# transmitter.net
KiCad netlist of a schematic drawn in Altium Designer
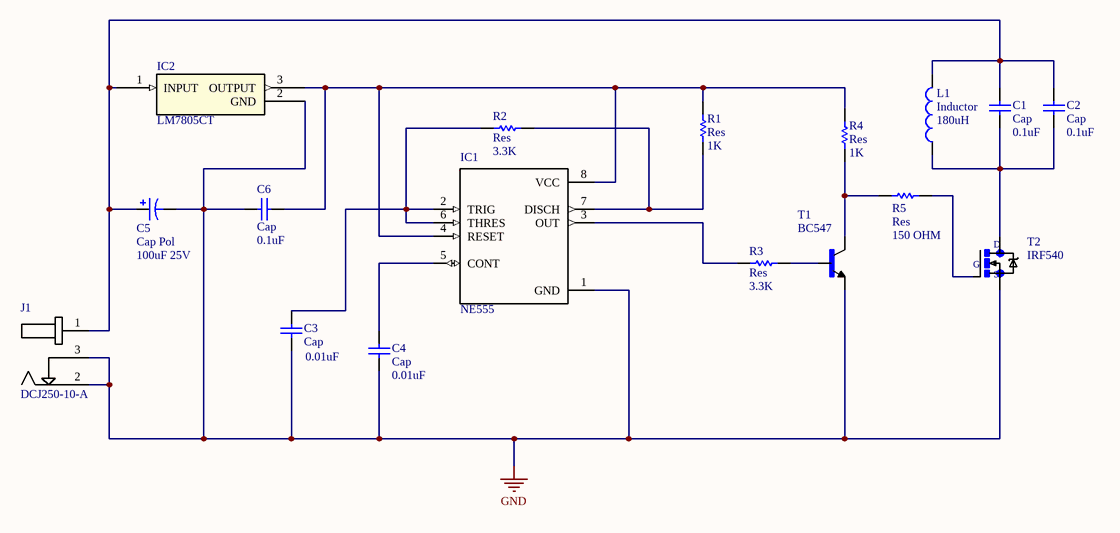
[diagram p0: transmitter.SchDoc]

(export (version "E")
  (design (tool "Eeschema 10.0.6"))
  (components
    (comp (ref "C1")
      (value "Cap")
      (footprint "RAD-0.3")
      (description "Capacitor")
      (fields (field (name "ALTIUM_VALUE") "0.1uF") (field (name "PUBLISHER") "Altium Limited"))
      (libsource (lib "Miscellaneous Devices") (part "Cap"))
    )
    (comp (ref "C2")
      (value "Cap")
      (footprint "RAD-0.3")
      (description "Capacitor")
      (fields (field (name "ALTIUM_VALUE") "0.1uF") (field (name "PUBLISHER") "Altium Limited"))
      (libsource (lib "Miscellaneous Devices") (part "Cap"))
    )
    (comp (ref "C3")
      (value "Cap")
      (footprint "RAD-0.3")
      (description "Capacitor")
      (fields (field (name "ALTIUM_VALUE") "0.01uF") (field (name "PUBLISHER") "Altium Limited"))
      (libsource (lib "Miscellaneous Devices") (part "Cap"))
    )
    (comp (ref "C4")
      (value "Cap")
      (footprint "RAD-0.3")
      (description "Capacitor")
      (fields (field (name "ALTIUM_VALUE") "0.01uF") (field (name "PUBLISHER") "Altium Limited"))
      (libsource (lib "Miscellaneous Devices") (part "Cap"))
    )
    (comp (ref "C5")
      (value "Cap Pol")
      (footprint "RB7.6-15")
      (description "Polarized Capacitor (Radial)")
      (fields (field (name "ALTIUM_VALUE") "100uF 25V") (field (name "PUBLISHER") "Altium Limited"))
      (libsource (lib "Miscellaneous Devices") (part "Cap Pol1"))
    )
    (comp (ref "C6")
      (value "Cap")
      (footprint "RAD-0.3")
      (description "Capacitor")
      (fields (field (name "ALTIUM_VALUE") "0.1uF") (field (name "PUBLISHER") "Altium Limited"))
      (libsource (lib "Miscellaneous Devices") (part "Cap"))
    )
    (comp (ref "IC1")
      (value "NE555")
      (footprint "NE555P:DIP8")
      (description "Precision timing circuits capable of producing accurate time delays or oscillation")
      (fields (field (name "MF") "Texas Instruments"))
      (libsource (lib "NE555") (part "NE555"))
    )
    (comp (ref "IC2")
      (value "LM7805CT")
      (footprint "LM7805CT:TO-220")
      (description "Imported")
      (libsource (lib "LM7805CT") (part "LM7805CT"))
    )
    (comp (ref "J1")
      (value "DCJ250-10-A")
      (footprint "DCJ250-10-A-XX-X_revA:DCJ250-10-A_XX-X_revA")
      (description "DC Power Jack, Thru-Hole, Horizontal, with Locating Pegs, D2.5mm")
      (libsource (lib "DCJ250-10-A_XX-X_revA") (part "DCJ250-10-A_XX-X_revA"))
    )
    (comp (ref "L1")
      (value "Inductor")
      (footprint "HDR1X2")
      (fields (field (name "ALTIUM_VALUE") "180uH") (field (name "PUBLISHER") "Altium Limited"))
      (libsource (lib "Miscellaneous Devices") (part "Inductor"))
    )
    (comp (ref "R1")
      (value "Res")
      (footprint "AXIAL-0.3")
      (description "Resistor")
      (fields (field (name "ALTIUM_VALUE") "1K") (field (name "PUBLISHER") "Altium Limited"))
      (libsource (lib "Miscellaneous Devices") (part "Res1"))
    )
    (comp (ref "R2")
      (value "Res")
      (footprint "AXIAL-0.3")
      (description "Resistor")
      (fields (field (name "ALTIUM_VALUE") "3.3K") (field (name "PUBLISHER") "Altium Limited"))
      (libsource (lib "Miscellaneous Devices") (part "Res1"))
    )
    (comp (ref "R3")
      (value "Res")
      (footprint "AXIAL-0.3")
      (description "Resistor")
      (fields (field (name "ALTIUM_VALUE") "3.3K") (field (name "PUBLISHER") "Altium Limited"))
      (libsource (lib "Miscellaneous Devices") (part "Res1"))
    )
    (comp (ref "R4")
      (value "Res")
      (footprint "AXIAL-0.3")
      (description "Resistor")
      (fields (field (name "ALTIUM_VALUE") "1K") (field (name "PUBLISHER") "Altium Limited"))
      (libsource (lib "Miscellaneous Devices") (part "Res1"))
    )
    (comp (ref "R5")
      (value "Res")
      (footprint "AXIAL-0.3")
      (description "Resistor")
      (fields (field (name "ALTIUM_VALUE") "150 OHM") (field (name "PUBLISHER") "Altium Limited"))
      (libsource (lib "Miscellaneous Devices") (part "Res1"))
    )
    (comp (ref "T1")
      (value "BC547")
      (footprint "TO-92")
      (description "Transistor NPN BC547 PHILIPS miliampere=100 TO92")
      (fields (field (name "MF") "ON Semiconductor"))
      (libsource (lib "BC547") (part "BC547"))
    )
    (comp (ref "T2")
      (value "IRF540")
      (footprint "TO220BV_IRF540(Primary)")
      (fields (field (name "MF") "Vishay Siliconix"))
      (libsource (lib "IRF540") (part "IRF540"))
    )
  )
  (nets
    (net (code "1") (name "GND") (class "Default")
      (node (ref "C3") (pin "1") (pinfunction "1_1") (pintype "passive"))
      (node (ref "C4") (pin "1") (pinfunction "1_1") (pintype "passive"))
      (node (ref "C5") (pin "2") (pinfunction "2_2") (pintype "passive"))
      (node (ref "C6") (pin "2") (pinfunction "2_2") (pintype "passive"))
      (node (ref "IC1") (pin "1") (pinfunction "GND_1") (pintype "power_in"))
      (node (ref "IC2") (pin "2") (pinfunction "GND_2") (pintype "power_in"))
      (node (ref "J1") (pin "2") (pintype "power_in"))
      (node (ref "J1") (pin "3") (pintype "power_in"))
      (node (ref "T1") (pin "1") (pinfunction "E_1") (pintype "passive"))
      (node (ref "T2") (pin "S") (pinfunction "S_S") (pintype "passive"))
    )
    (net (code "2") (name "Net-(C1-Pad1)") (class "Default")
      (node (ref "C1") (pin "1") (pinfunction "1_1") (pintype "passive"))
      (node (ref "C2") (pin "1") (pinfunction "1_1") (pintype "passive"))
      (node (ref "L1") (pin "1") (pinfunction "1_1") (pintype "passive"))
      (node (ref "T2") (pin "D") (pinfunction "D_D") (pintype "passive"))
    )
    (net (code "3") (name "Net-(IC1-CONT)") (class "Default")
      (node (ref "C4") (pin "2") (pinfunction "2_2") (pintype "passive"))
      (node (ref "IC1") (pin "5") (pinfunction "CONT_5") (pintype "bidirectional"))
    )
    (net (code "4") (name "Net-(IC1-DISCH)") (class "Default")
      (node (ref "IC1") (pin "7") (pinfunction "DISCH_7") (pintype "output"))
      (node (ref "R1") (pin "1") (pinfunction "1_1") (pintype "passive"))
      (node (ref "R2") (pin "2") (pinfunction "2_2") (pintype "passive"))
    )
    (net (code "5") (name "Net-(IC1-OUT)") (class "Default")
      (node (ref "IC1") (pin "3") (pinfunction "OUT_3") (pintype "output"))
      (node (ref "R3") (pin "1") (pinfunction "1_1") (pintype "passive"))
    )
    (net (code "6") (name "Net-(IC1-RESET)") (class "Default")
      (node (ref "C6") (pin "1") (pinfunction "1_1") (pintype "passive"))
      (node (ref "IC1") (pin "4") (pinfunction "RESET_4") (pintype "input"))
      (node (ref "IC1") (pin "8") (pinfunction "VCC_8") (pintype "power_in"))
      (node (ref "IC2") (pin "3") (pinfunction "OUTPUT_3") (pintype "output"))
      (node (ref "R1") (pin "2") (pinfunction "2_2") (pintype "passive"))
      (node (ref "R4") (pin "2") (pinfunction "2_2") (pintype "passive"))
    )
    (net (code "7") (name "Net-(IC1-THRES)") (class "Default")
      (node (ref "C3") (pin "2") (pinfunction "2_2") (pintype "passive"))
      (node (ref "IC1") (pin "2") (pinfunction "TRIG_2") (pintype "input"))
      (node (ref "IC1") (pin "6") (pinfunction "THRES_6") (pintype "input"))
      (node (ref "R2") (pin "1") (pinfunction "1_1") (pintype "passive"))
    )
    (net (code "8") (name "Net-(IC2-INPUT)") (class "Default")
      (node (ref "C1") (pin "2") (pinfunction "2_2") (pintype "passive"))
      (node (ref "C2") (pin "2") (pinfunction "2_2") (pintype "passive"))
      (node (ref "C5") (pin "1") (pinfunction "1_1") (pintype "passive"))
      (node (ref "IC2") (pin "1") (pinfunction "INPUT_1") (pintype "input"))
      (node (ref "J1") (pin "1") (pintype "power_in"))
      (node (ref "L1") (pin "2") (pinfunction "2_2") (pintype "passive"))
    )
    (net (code "9") (name "Net-(R5-Pad2)") (class "Default")
      (node (ref "R5") (pin "2") (pinfunction "2_2") (pintype "passive"))
      (node (ref "T2") (pin "G") (pinfunction "G_G") (pintype "passive"))
    )
    (net (code "10") (name "Net-(T1-B)") (class "Default")
      (node (ref "R3") (pin "2") (pinfunction "2_2") (pintype "passive"))
      (node (ref "T1") (pin "2") (pinfunction "B_2") (pintype "passive"))
    )
    (net (code "11") (name "Net-(T1-C)") (class "Default")
      (node (ref "R4") (pin "1") (pinfunction "1_1") (pintype "passive"))
      (node (ref "R5") (pin "1") (pinfunction "1_1") (pintype "passive"))
      (node (ref "T1") (pin "3") (pinfunction "C_3") (pintype "passive"))
    )
  )
)
